# Fonte_Chaveada_ISL6236.net
KiCad netlist of a schematic drawn in Altium Designer
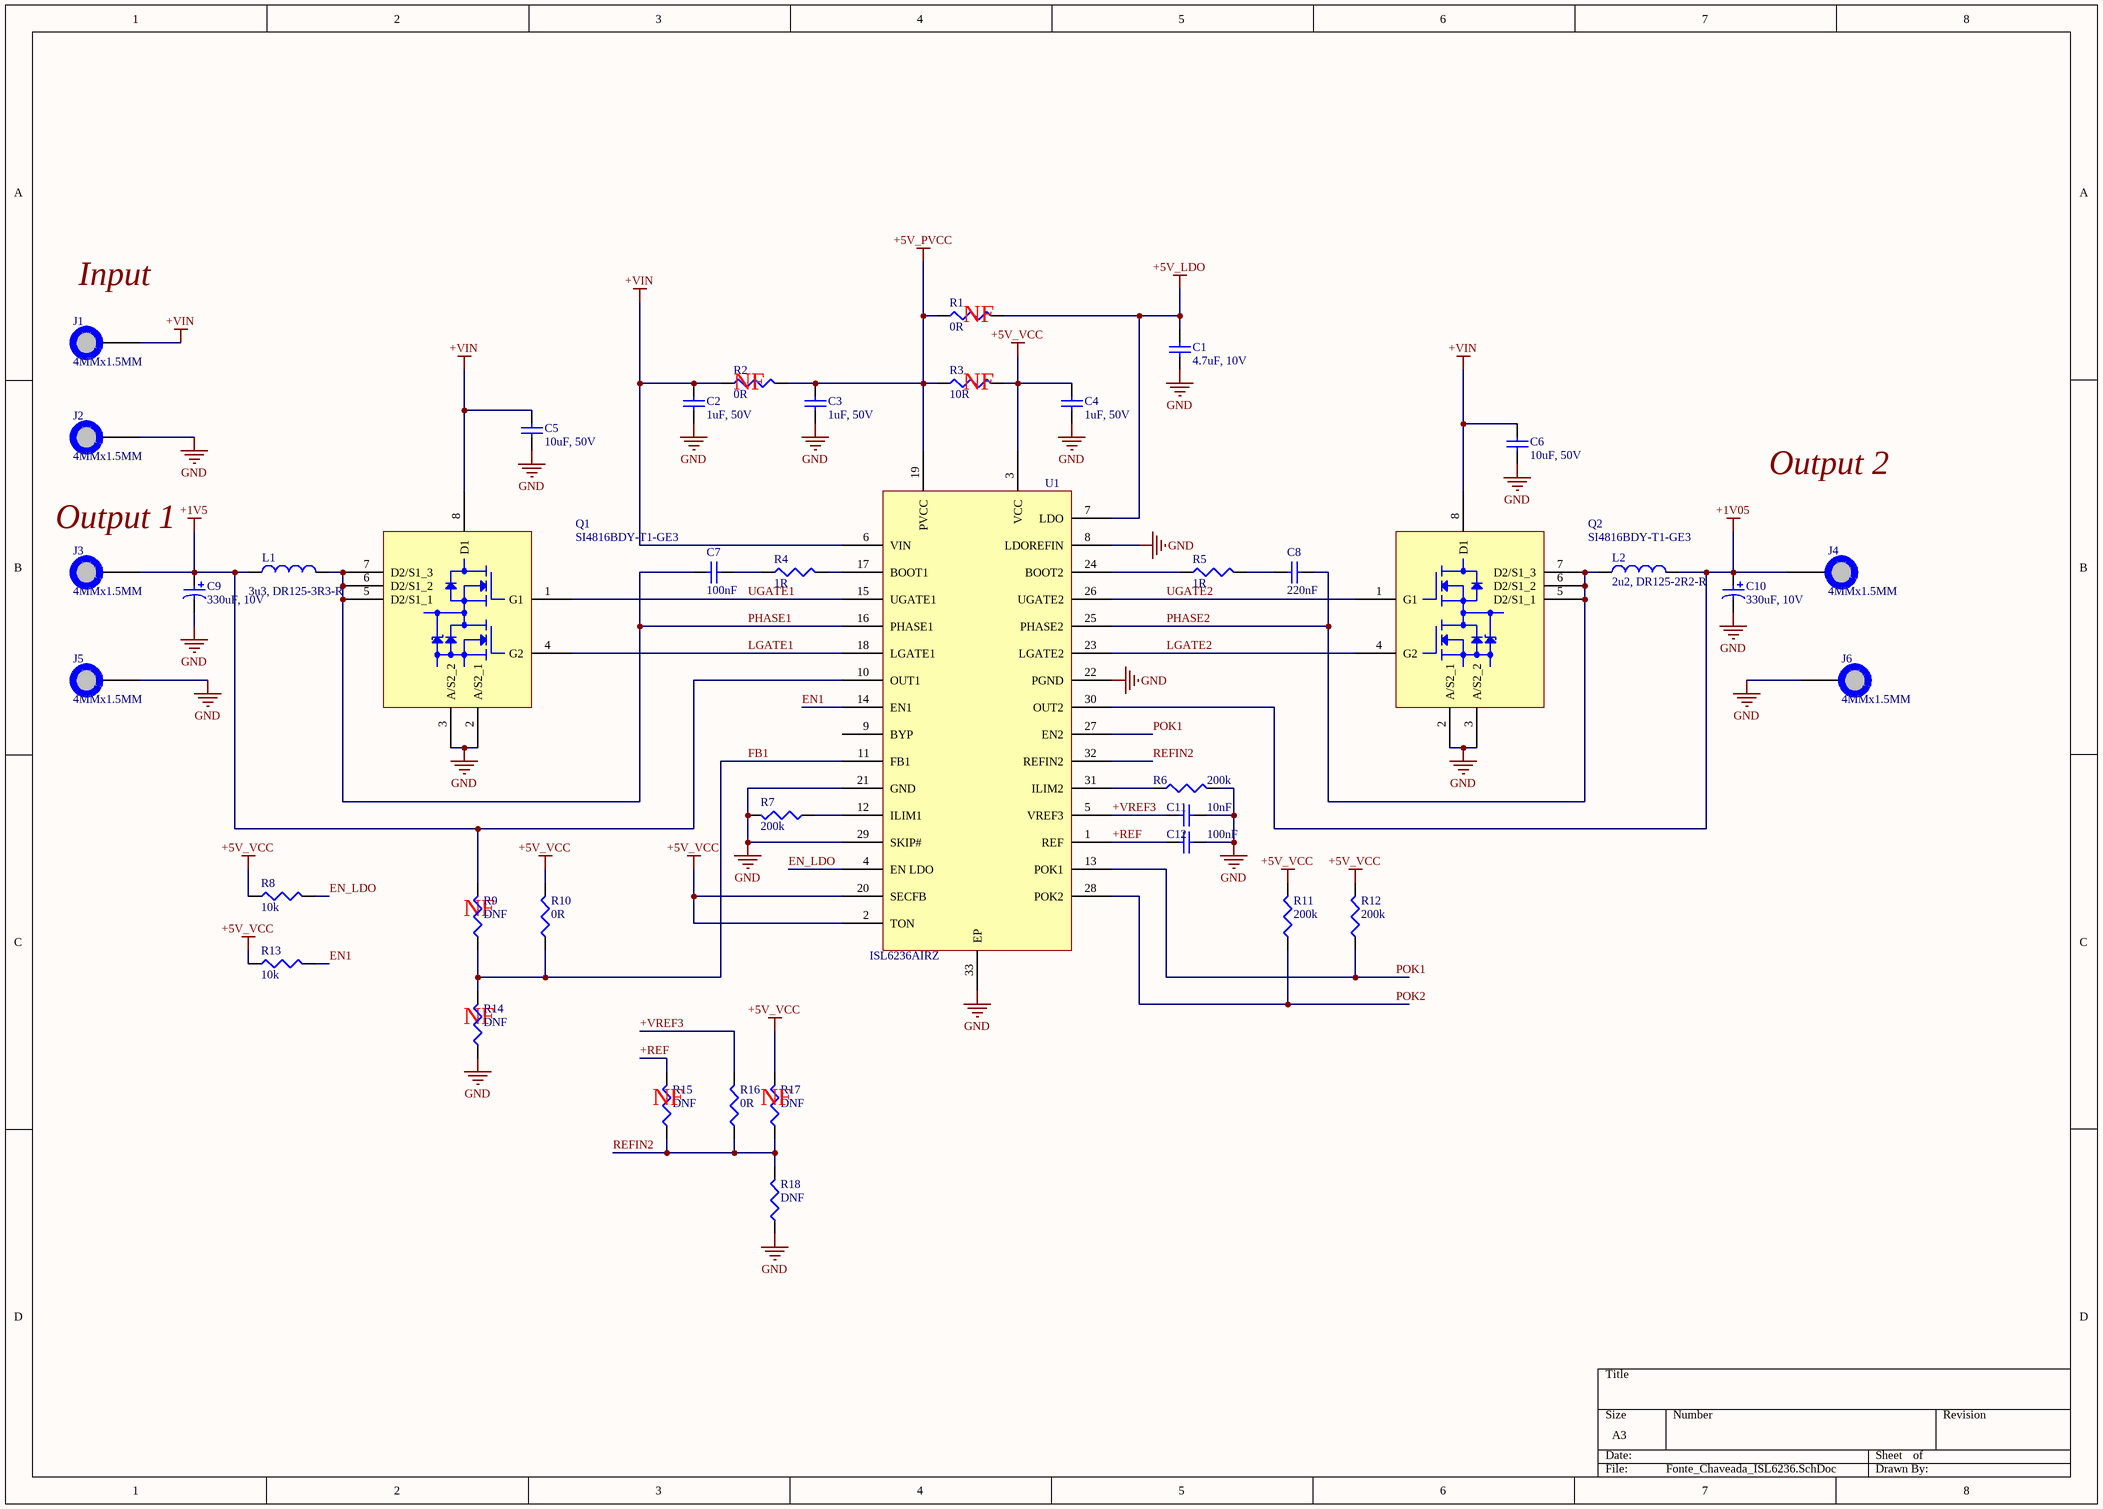
[diagram p0: Fonte_Chaveada_ISL6236.SchDoc]

(export (version "E")
  (design (tool "Eeschema 10.0.6"))
  (components
    (comp (ref "C1")
      (value "4.7uF, 10V")
      (footprint "C1206")
      (fields
        (field (name "MANUFACTURER") "TDK")
        (field (name "MANUFACTURER PART NUMBER") "C3216X5R1A475K")
        (field (name "TOLERANCE") "10%")
      )
      (libsource (lib "Fonte_Chaveada_ISL6236") (part "C3216X5R1A475K"))
    )
    (comp (ref "C2")
      (value "1uF, 50V")
      (footprint "C0805")
      (description "CAP CER 1UF 50V X7R 0805")
      (fields
        (field (name "MANUFACTURER") "TDK")
        (field (name "MANUFACTURER PART NUMBER") "C2012X7R1H105K125AB")
      )
      (libsource (lib "Fonte_Chaveada_ISL6236") (part "C2012X7R1H105K125AB"))
    )
    (comp (ref "C3")
      (value "1uF, 50V")
      (footprint "C0805")
      (description "CAP CER 1UF 50V X7R 0805")
      (fields
        (field (name "MANUFACTURER") "TDK")
        (field (name "MANUFACTURER PART NUMBER") "C2012X7R1H105K125AB")
      )
      (libsource (lib "Fonte_Chaveada_ISL6236") (part "C2012X7R1H105K125AB"))
    )
    (comp (ref "C4")
      (value "1uF, 50V")
      (footprint "C0805")
      (description "CAP CER 1UF 50V X7R 0805")
      (fields
        (field (name "MANUFACTURER") "TDK")
        (field (name "MANUFACTURER PART NUMBER") "C2012X7R1H105K125AB")
      )
      (libsource (lib "Fonte_Chaveada_ISL6236") (part "C2012X7R1H105K125AB"))
    )
    (comp (ref "C5")
      (value "10uF, 50V")
      (footprint "C1210")
      (description "CAP CER 10UF 50V X5R 1210")
      (fields
        (field (name "MANUFACTURER") "Taiyo Yuden")
        (field (name "MANUFACTURER PART NUMBER") "UMK325BJ106MM-T")
      )
      (libsource (lib "Fonte_Chaveada_ISL6236") (part "UMK325BJ106MM-T"))
    )
    (comp (ref "C6")
      (value "10uF, 50V")
      (footprint "C1210")
      (description "CAP CER 10UF 50V X5R 1210")
      (fields
        (field (name "MANUFACTURER") "Taiyo Yuden")
        (field (name "MANUFACTURER PART NUMBER") "UMK325BJ106MM-T")
      )
      (libsource (lib "Fonte_Chaveada_ISL6236") (part "UMK325BJ106MM-T"))
    )
    (comp (ref "C7")
      (value "100nF")
      (footprint "C0805")
      (description "CAP CER 0.1UF 50V X7R 0805")
      (fields
        (field (name "MANUFACTURER") "TDK")
        (field (name "MANUFACTURER PART NUMBER") "C2012X7R1H104K085AA")
      )
      (libsource (lib "Fonte_Chaveada_ISL6236") (part "C2012X7R1H104K085AA"))
    )
    (comp (ref "C8")
      (value "220nF")
      (footprint "C0805")
      (description "CAP CER 0.22UF 50V X7R 0805")
      (fields
        (field (name "MANUFACTURER") "TDK")
        (field (name "MANUFACTURER PART NUMBER") "C2012X7R1H224K125AA")
      )
      (libsource (lib "Fonte_Chaveada_ISL6236") (part "C2012X7R1H224K125AA"))
    )
    (comp (ref "C9")
      (value "330uF, 10V")
      (footprint "7343-43")
      (description "Tantalum Capacitors - Polymer SMD 330uF 10volts 20%")
      (fields
        (field (name "MANUFACTURER") "KEMET")
        (field (name "MANUFACTURER PART NUMBER") "T530X337M010ATE004")
      )
      (libsource (lib "Fonte_Chaveada_ISL6236") (part "T530X337M010ATE004"))
    )
    (comp (ref "C10")
      (value "330uF, 10V")
      (footprint "7343-43")
      (description "Tantalum Capacitors - Polymer SMD 330uF 10volts 20%")
      (fields
        (field (name "MANUFACTURER") "KEMET")
        (field (name "MANUFACTURER PART NUMBER") "T530X337M010ATE004")
      )
      (libsource (lib "Fonte_Chaveada_ISL6236") (part "T530X337M010ATE004"))
    )
    (comp (ref "C11")
      (value "10nF")
      (footprint "C0805")
      (description "CAP CER 10000PF 50V X7R 0805")
      (fields
        (field (name "MANUFACTURER") "Vishay Vitramon")
        (field (name "MANUFACTURER PART NUMBER") "VJ0805Y103KNAAO")
      )
      (libsource (lib "Fonte_Chaveada_ISL6236") (part "VJ0805Y103KNAAO"))
    )
    (comp (ref "C12")
      (value "100nF")
      (footprint "C0805")
      (description "CAP CER 0.1UF 50V X7R 0805")
      (fields
        (field (name "MANUFACTURER") "TDK")
        (field (name "MANUFACTURER PART NUMBER") "C2012X7R1H104K085AA")
      )
      (libsource (lib "Fonte_Chaveada_ISL6236") (part "C2012X7R1H104K085AA"))
    )
    (comp (ref "J1")
      (value "4MMx1.5MM")
      (footprint "PAD")
      (libsource (lib "Fonte_Chaveada_ISL6236") (part "PAD com furo"))
    )
    (comp (ref "J2")
      (value "4MMx1.5MM")
      (footprint "PAD")
      (libsource (lib "Fonte_Chaveada_ISL6236") (part "PAD com furo"))
    )
    (comp (ref "J3")
      (value "4MMx1.5MM")
      (footprint "PAD")
      (libsource (lib "Fonte_Chaveada_ISL6236") (part "PAD com furo"))
    )
    (comp (ref "J4")
      (value "4MMx1.5MM")
      (footprint "PAD")
      (libsource (lib "Fonte_Chaveada_ISL6236") (part "PAD com furo"))
    )
    (comp (ref "J5")
      (value "4MMx1.5MM")
      (footprint "PAD")
      (libsource (lib "Fonte_Chaveada_ISL6236") (part "PAD com furo"))
    )
    (comp (ref "J6")
      (value "4MMx1.5MM")
      (footprint "PAD")
      (libsource (lib "Fonte_Chaveada_ISL6236") (part "PAD com furo"))
    )
    (comp (ref "L1")
      (value "3u3, DR125-3R3-R")
      (footprint "DR125")
      (description "COILTRONICS   DR125-3R3-R   Surface Mount Power Inductor, DR Series, 3.3 H,  20%, Shielded, 9.26 A")
      (fields
        (field (name "MANUFACTURER") "Eaton Coiltronics")
        (field (name "MANUFACTURER PART NUMBER") "DR125-3R3-R")
      )
      (libsource (lib "Fonte_Chaveada_ISL6236") (part "DR125-3R3-R"))
    )
    (comp (ref "L2")
      (value "2u2, DR125-2R2-R")
      (footprint "DR125")
      (description "Fixed Inductors 2.2uH 15A 0.0045ohms")
      (fields
        (field (name "MANUFACTURER") "Eaton Cooper")
        (field (name "MANUFACTURER PART NUMBER") "DR125-2R2-R")
      )
      (libsource (lib "Fonte_Chaveada_ISL6236") (part "DR125-2R2-R"))
    )
    (comp (ref "Q1")
      (value "SI4816BDY-T1-GE3")
      (footprint "SO-8")
      (description "MOSFET 2N-CH 30V 5.8A 8-SOIC")
      (fields (field (name "MANUFACTURER") "Vishay Siliconix"))
      (libsource (lib "Fonte_Chaveada_ISL6236") (part "SI4816BDY-T1-GE3"))
    )
    (comp (ref "Q2")
      (value "SI4816BDY-T1-GE3")
      (footprint "SO-8")
      (description "MOSFET 2N-CH 30V 5.8A 8-SOIC")
      (fields (field (name "MANUFACTURER") "Vishay Siliconix"))
      (libsource (lib "") (part "SI4816BDY-T1-GE3_1"))
    )
    (comp (ref "R1")
      (value "0R")
      (footprint "R0805")
      (description "Res Thick Film 0805 0 Ohm Molded SMD SMD Embossed Carrier T/R")
      (fields
        (field (name "MANUFACTURER") "Panasonic")
        (field (name "MANUFACTURER PART NUMBER") "ERJ6GEY0R00V")
      )
      (libsource (lib "Fonte_Chaveada_ISL6236") (part "ERJ6GEY0R00V"))
    )
    (comp (ref "R2")
      (value "0R")
      (footprint "R0805")
      (description "Res Thick Film 0805 0 Ohm Molded SMD SMD Embossed Carrier T/R")
      (fields
        (field (name "MANUFACTURER") "Panasonic")
        (field (name "MANUFACTURER PART NUMBER") "ERJ6GEY0R00V")
      )
      (libsource (lib "Fonte_Chaveada_ISL6236") (part "ERJ6GEY0R00V"))
    )
    (comp (ref "R3")
      (value "10R")
      (footprint "R0805")
      (description "Res Thick Film 0805 10 Ohm 5% 0.125W(1/8W) ±200ppm/C Molded SMD Automotive Punched T/R")
      (fields
        (field (name "MANUFACTURER") "Panasonic")
        (field (name "MANUFACTURER PART NUMBER") "ERJ6GEYJ100V")
      )
      (libsource (lib "Fonte_Chaveada_ISL6236") (part "ERJ6GEYJ100V"))
    )
    (comp (ref "R4")
      (value "1R")
      (footprint "R0805")
      (description "Res Thick Film 0805 1 Ohm 1% 0.125W(1/8W) ±200ppm/C Molded SMD Automotive Punched T/R")
      (fields
        (field (name "MANUFACTURER") "Panasonic")
        (field (name "MANUFACTURER PART NUMBER") "ERJ6RQF1R0V")
      )
      (libsource (lib "Fonte_Chaveada_ISL6236") (part "ERJ6RQF1R0V"))
    )
    (comp (ref "R5")
      (value "1R")
      (footprint "R0805")
      (description "Res Thick Film 0805 1 Ohm 1% 0.125W(1/8W) ±200ppm/C Molded SMD Automotive Punched T/R")
      (fields
        (field (name "MANUFACTURER") "Panasonic")
        (field (name "MANUFACTURER PART NUMBER") "ERJ6RQF1R0V")
      )
      (libsource (lib "Fonte_Chaveada_ISL6236") (part "ERJ6RQF1R0V"))
    )
    (comp (ref "R6")
      (value "200k")
      (footprint "R0805")
      (description "Res Thick Film 0805 200K Ohm 1% 1/8W ±100ppm/C Molded SMD Punched Carrier T/R")
      (fields
        (field (name "MANUFACTURER") "Panasonic")
        (field (name "MANUFACTURER PART NUMBER") "ERJ6ENF2003V")
      )
      (libsource (lib "Fonte_Chaveada_ISL6236") (part "ERJ6ENF2003V"))
    )
    (comp (ref "R7")
      (value "200k")
      (footprint "R0805")
      (description "Res Thick Film 0805 200K Ohm 1% 1/8W ±100ppm/C Molded SMD Punched Carrier T/R")
      (fields
        (field (name "MANUFACTURER") "Panasonic")
        (field (name "MANUFACTURER PART NUMBER") "ERJ6ENF2003V")
      )
      (libsource (lib "Fonte_Chaveada_ISL6236") (part "ERJ6ENF2003V"))
    )
    (comp (ref "R8")
      (value "10k")
      (footprint "R0805")
      (description "Res Thick Film 0805 10K Ohm 5% 0.125W(1/8W) ±200ppm/C Molded SMD Automotive Punched T/R")
      (fields
        (field (name "MANUFACTURER") "Panasonic")
        (field (name "MANUFACTURER PART NUMBER") "ERJ6GEYJ103V")
      )
      (libsource (lib "Fonte_Chaveada_ISL6236") (part "ERJ6GEYJ103V"))
    )
    (comp (ref "R9")
      (value "DNF")
      (footprint "R0805")
      (libsource (lib "Fonte_Chaveada_ISL6236") (part "RES"))
    )
    (comp (ref "R10")
      (value "0R")
      (footprint "R0805")
      (description "Res Thick Film 0805 0 Ohm Molded SMD SMD Embossed Carrier T/R")
      (fields
        (field (name "MANUFACTURER") "Panasonic")
        (field (name "MANUFACTURER PART NUMBER") "ERJ6GEY0R00V")
      )
      (libsource (lib "Fonte_Chaveada_ISL6236") (part "ERJ6GEY0R00V"))
    )
    (comp (ref "R11")
      (value "200k")
      (footprint "R0805")
      (description "Res Thick Film 0805 200K Ohm 1% 1/8W ±100ppm/C Molded SMD Punched Carrier T/R")
      (fields
        (field (name "MANUFACTURER") "Panasonic")
        (field (name "MANUFACTURER PART NUMBER") "ERJ6ENF2003V")
      )
      (libsource (lib "Fonte_Chaveada_ISL6236") (part "ERJ6ENF2003V"))
    )
    (comp (ref "R12")
      (value "200k")
      (footprint "R0805")
      (description "Res Thick Film 0805 200K Ohm 1% 1/8W ±100ppm/C Molded SMD Punched Carrier T/R")
      (fields
        (field (name "MANUFACTURER") "Panasonic")
        (field (name "MANUFACTURER PART NUMBER") "ERJ6ENF2003V")
      )
      (libsource (lib "Fonte_Chaveada_ISL6236") (part "ERJ6ENF2003V"))
    )
    (comp (ref "R13")
      (value "10k")
      (footprint "R0805")
      (description "Res Thick Film 0805 10K Ohm 5% 0.125W(1/8W) ±200ppm/C Molded SMD Automotive Punched T/R")
      (fields
        (field (name "MANUFACTURER") "Panasonic")
        (field (name "MANUFACTURER PART NUMBER") "ERJ6GEYJ103V")
      )
      (libsource (lib "Fonte_Chaveada_ISL6236") (part "ERJ6GEYJ103V"))
    )
    (comp (ref "R14")
      (value "DNF")
      (footprint "R0805")
      (libsource (lib "Fonte_Chaveada_ISL6236") (part "RES"))
    )
    (comp (ref "R15")
      (value "DNF")
      (footprint "R0805")
      (libsource (lib "Fonte_Chaveada_ISL6236") (part "RES"))
    )
    (comp (ref "R16")
      (value "0R")
      (footprint "R0805")
      (description "Res Thick Film 0805 0 Ohm Molded SMD SMD Embossed Carrier T/R")
      (fields
        (field (name "MANUFACTURER") "Panasonic")
        (field (name "MANUFACTURER PART NUMBER") "ERJ6GEY0R00V")
      )
      (libsource (lib "Fonte_Chaveada_ISL6236") (part "ERJ6GEY0R00V"))
    )
    (comp (ref "R17")
      (value "DNF")
      (footprint "R0805")
      (libsource (lib "Fonte_Chaveada_ISL6236") (part "RES"))
    )
    (comp (ref "R18")
      (value "DNF")
      (footprint "R0805")
      (libsource (lib "Fonte_Chaveada_ISL6236") (part "RES"))
    )
    (comp (ref "U1")
      (value "ISL6236AIRZ")
      (footprint "L32.5x5B")
      (description "IC MAIN PWR CTRLR QUAD 32-QFN")
      (fields (field (name "MANUFACTURER") "Intersil"))
      (libsource (lib "Fonte_Chaveada_ISL6236") (part "ISL6236AIRZ"))
    )
  )
  (nets
    (net (code "1") (name "+1V05") (class "Default")
      (node (ref "C10") (pin "1") (pinfunction "1_1") (pintype "passive"))
      (node (ref "J4") (pin "1") (pinfunction "1_1") (pintype "passive"))
      (node (ref "L2") (pin "2") (pinfunction "2_2") (pintype "passive"))
      (node (ref "U1") (pin "30") (pinfunction "OUT2_30") (pintype "passive"))
    )
    (net (code "2") (name "+1V5") (class "Default")
      (node (ref "C9") (pin "1") (pinfunction "1_1") (pintype "passive"))
      (node (ref "J3") (pin "1") (pinfunction "1_1") (pintype "passive"))
      (node (ref "L1") (pin "1") (pinfunction "1_1") (pintype "passive"))
      (node (ref "R9") (pin "2") (pinfunction "2_2") (pintype "passive"))
      (node (ref "U1") (pin "10") (pinfunction "OUT1_10") (pintype "passive"))
    )
    (net (code "3") (name "+5V_LDO") (class "Default")
      (node (ref "C1") (pin "2") (pinfunction "2_2") (pintype "passive"))
      (node (ref "R1") (pin "2") (pinfunction "2_2") (pintype "passive"))
      (node (ref "U1") (pin "7") (pinfunction "LDO_7") (pintype "passive"))
    )
    (net (code "4") (name "+5V_PVCC") (class "Default")
      (node (ref "C3") (pin "2") (pinfunction "2_2") (pintype "passive"))
      (node (ref "R1") (pin "1") (pinfunction "1_1") (pintype "passive"))
      (node (ref "R2") (pin "2") (pinfunction "2_2") (pintype "passive"))
      (node (ref "R3") (pin "1") (pinfunction "1_1") (pintype "passive"))
      (node (ref "U1") (pin "19") (pinfunction "PVCC_19") (pintype "passive"))
    )
    (net (code "5") (name "+5V_VCC") (class "Default")
      (node (ref "C4") (pin "2") (pinfunction "2_2") (pintype "passive"))
      (node (ref "R10") (pin "2") (pinfunction "2_2") (pintype "passive"))
      (node (ref "R11") (pin "2") (pinfunction "2_2") (pintype "passive"))
      (node (ref "R12") (pin "2") (pinfunction "2_2") (pintype "passive"))
      (node (ref "R13") (pin "1") (pinfunction "1_1") (pintype "passive"))
      (node (ref "R17") (pin "2") (pinfunction "2_2") (pintype "passive"))
      (node (ref "R3") (pin "2") (pinfunction "2_2") (pintype "passive"))
      (node (ref "R8") (pin "1") (pinfunction "1_1") (pintype "passive"))
      (node (ref "U1") (pin "2") (pinfunction "TON_2") (pintype "passive"))
      (node (ref "U1") (pin "20") (pinfunction "SECFB_20") (pintype "passive"))
      (node (ref "U1") (pin "3") (pinfunction "VCC_3") (pintype "passive"))
    )
    (net (code "6") (name "+VIN") (class "Default")
      (node (ref "C2") (pin "2") (pinfunction "2_2") (pintype "passive"))
      (node (ref "C5") (pin "2") (pinfunction "2_2") (pintype "passive"))
      (node (ref "C6") (pin "2") (pinfunction "2_2") (pintype "passive"))
      (node (ref "J1") (pin "1") (pinfunction "1_1") (pintype "passive"))
      (node (ref "Q1") (pin "8") (pinfunction "D1_8") (pintype "passive"))
      (node (ref "Q2") (pin "8") (pinfunction "D1_8") (pintype "passive"))
      (node (ref "R2") (pin "1") (pinfunction "1_1") (pintype "passive"))
      (node (ref "U1") (pin "6") (pinfunction "VIN_6") (pintype "passive"))
    )
    (net (code "7") (name "/+REF") (class "Default")
      (node (ref "C12") (pin "1") (pinfunction "1_1") (pintype "passive"))
      (node (ref "R15") (pin "2") (pinfunction "2_2") (pintype "passive"))
      (node (ref "U1") (pin "1") (pinfunction "REF_1") (pintype "passive"))
    )
    (net (code "8") (name "/+VREF3") (class "Default")
      (node (ref "C11") (pin "1") (pinfunction "1_1") (pintype "passive"))
      (node (ref "R16") (pin "2") (pinfunction "2_2") (pintype "passive"))
      (node (ref "U1") (pin "5") (pinfunction "VREF3_5") (pintype "passive"))
    )
    (net (code "9") (name "/EN1") (class "Default")
      (node (ref "R13") (pin "2") (pinfunction "2_2") (pintype "passive"))
      (node (ref "U1") (pin "14") (pinfunction "EN1_14") (pintype "passive"))
    )
    (net (code "10") (name "/EN_LDO") (class "Default")
      (node (ref "R8") (pin "2") (pinfunction "2_2") (pintype "passive"))
      (node (ref "U1") (pin "4") (pinfunction "EN_LDO_4") (pintype "passive"))
    )
    (net (code "11") (name "/FB1") (class "Default")
      (node (ref "R10") (pin "1") (pinfunction "1_1") (pintype "passive"))
      (node (ref "R14") (pin "2") (pinfunction "2_2") (pintype "passive"))
      (node (ref "R9") (pin "1") (pinfunction "1_1") (pintype "passive"))
      (node (ref "U1") (pin "11") (pinfunction "FB1_11") (pintype "passive"))
    )
    (net (code "12") (name "/LGATE1") (class "Default")
      (node (ref "Q1") (pin "4") (pinfunction "G2_4") (pintype "passive"))
      (node (ref "U1") (pin "18") (pinfunction "LGATE1_18") (pintype "passive"))
    )
    (net (code "13") (name "/LGATE2") (class "Default")
      (node (ref "Q2") (pin "4") (pinfunction "G2_4") (pintype "passive"))
      (node (ref "U1") (pin "23") (pinfunction "LGATE2_23") (pintype "passive"))
    )
    (net (code "14") (name "/PHASE1") (class "Default")
      (node (ref "C7") (pin "1") (pinfunction "1_1") (pintype "passive"))
      (node (ref "L1") (pin "2") (pinfunction "2_2") (pintype "passive"))
      (node (ref "Q1") (pin "5") (pinfunction "D2/S1_1_5") (pintype "passive"))
      (node (ref "Q1") (pin "6") (pinfunction "D2/S1_2_6") (pintype "passive"))
      (node (ref "Q1") (pin "7") (pinfunction "D2/S1_3_7") (pintype "passive"))
      (node (ref "U1") (pin "16") (pinfunction "PHASE1_16") (pintype "passive"))
    )
    (net (code "15") (name "/PHASE2") (class "Default")
      (node (ref "C8") (pin "2") (pinfunction "2_2") (pintype "passive"))
      (node (ref "L2") (pin "1") (pinfunction "1_1") (pintype "passive"))
      (node (ref "Q2") (pin "5") (pinfunction "D2/S1_1_5") (pintype "passive"))
      (node (ref "Q2") (pin "6") (pinfunction "D2/S1_2_6") (pintype "passive"))
      (node (ref "Q2") (pin "7") (pinfunction "D2/S1_3_7") (pintype "passive"))
      (node (ref "U1") (pin "25") (pinfunction "PHASE2_25") (pintype "passive"))
    )
    (net (code "16") (name "/POK1") (class "Default")
      (node (ref "R12") (pin "1") (pinfunction "1_1") (pintype "passive"))
      (node (ref "U1") (pin "13") (pinfunction "POK1_13") (pintype "passive"))
      (node (ref "U1") (pin "27") (pinfunction "EN2_27") (pintype "passive"))
    )
    (net (code "17") (name "/POK2") (class "Default")
      (node (ref "R11") (pin "1") (pinfunction "1_1") (pintype "passive"))
      (node (ref "U1") (pin "28") (pinfunction "POK2_28") (pintype "passive"))
    )
    (net (code "18") (name "/REFIN2") (class "Default")
      (node (ref "R15") (pin "1") (pinfunction "1_1") (pintype "passive"))
      (node (ref "R16") (pin "1") (pinfunction "1_1") (pintype "passive"))
      (node (ref "R17") (pin "1") (pinfunction "1_1") (pintype "passive"))
      (node (ref "R18") (pin "2") (pinfunction "2_2") (pintype "passive"))
      (node (ref "U1") (pin "32") (pinfunction "REFIN2_32") (pintype "passive"))
    )
    (net (code "19") (name "/UGATE1") (class "Default")
      (node (ref "Q1") (pin "1") (pinfunction "G1_1") (pintype "passive"))
      (node (ref "U1") (pin "15") (pinfunction "UGATE1_15") (pintype "passive"))
    )
    (net (code "20") (name "/UGATE2") (class "Default")
      (node (ref "Q2") (pin "1") (pinfunction "G1_1") (pintype "passive"))
      (node (ref "U1") (pin "26") (pinfunction "UGATE2_26") (pintype "passive"))
    )
    (net (code "21") (name "GND") (class "Default")
      (node (ref "C1") (pin "1") (pinfunction "1_1") (pintype "passive"))
      (node (ref "C10") (pin "2") (pinfunction "2_2") (pintype "passive"))
      (node (ref "C11") (pin "2") (pinfunction "2_2") (pintype "passive"))
      (node (ref "C12") (pin "2") (pinfunction "2_2") (pintype "passive"))
      (node (ref "C2") (pin "1") (pinfunction "1_1") (pintype "passive"))
      (node (ref "C3") (pin "1") (pinfunction "1_1") (pintype "passive"))
      (node (ref "C4") (pin "1") (pinfunction "1_1") (pintype "passive"))
      (node (ref "C5") (pin "1") (pinfunction "1_1") (pintype "passive"))
      (node (ref "C6") (pin "1") (pinfunction "1_1") (pintype "passive"))
      (node (ref "C9") (pin "2") (pinfunction "2_2") (pintype "passive"))
      (node (ref "J2") (pin "1") (pinfunction "1_1") (pintype "passive"))
      (node (ref "J5") (pin "1") (pinfunction "1_1") (pintype "passive"))
      (node (ref "J6") (pin "1") (pinfunction "1_1") (pintype "passive"))
      (node (ref "Q1") (pin "2") (pinfunction "A/S2_1_2") (pintype "passive"))
      (node (ref "Q1") (pin "3") (pinfunction "A/S2_2_3") (pintype "passive"))
      (node (ref "Q2") (pin "2") (pinfunction "A/S2_1_2") (pintype "passive"))
      (node (ref "Q2") (pin "3") (pinfunction "A/S2_2_3") (pintype "passive"))
      (node (ref "R14") (pin "1") (pinfunction "1_1") (pintype "passive"))
      (node (ref "R18") (pin "1") (pinfunction "1_1") (pintype "passive"))
      (node (ref "R6") (pin "2") (pinfunction "2_2") (pintype "passive"))
      (node (ref "R7") (pin "2") (pinfunction "2_2") (pintype "passive"))
      (node (ref "U1") (pin "21") (pinfunction "GND_21") (pintype "passive"))
      (node (ref "U1") (pin "22") (pinfunction "PGND_22") (pintype "passive"))
      (node (ref "U1") (pin "29") (pinfunction "SKIP#_29") (pintype "passive"))
      (node (ref "U1") (pin "33") (pinfunction "EP_33") (pintype "passive"))
      (node (ref "U1") (pin "8") (pinfunction "LDOREFIN_8") (pintype "passive"))
    )
    (net (code "22") (name "Net-(C7-Pad2)") (class "Default")
      (node (ref "C7") (pin "2") (pinfunction "2_2") (pintype "passive"))
      (node (ref "R4") (pin "1") (pinfunction "1_1") (pintype "passive"))
    )
    (net (code "23") (name "Net-(C8-Pad1)") (class "Default")
      (node (ref "C8") (pin "1") (pinfunction "1_1") (pintype "passive"))
      (node (ref "R5") (pin "2") (pinfunction "2_2") (pintype "passive"))
    )
    (net (code "24") (name "Net-(U1-BOOT1)") (class "Default")
      (node (ref "R4") (pin "2") (pinfunction "2_2") (pintype "passive"))
      (node (ref "U1") (pin "17") (pinfunction "BOOT1_17") (pintype "passive"))
    )
    (net (code "25") (name "Net-(U1-BOOT2)") (class "Default")
      (node (ref "R5") (pin "1") (pinfunction "1_1") (pintype "passive"))
      (node (ref "U1") (pin "24") (pinfunction "BOOT2_24") (pintype "passive"))
    )
    (net (code "26") (name "Net-(U1-ILIM1)") (class "Default")
      (node (ref "R7") (pin "1") (pinfunction "1_1") (pintype "passive"))
      (node (ref "U1") (pin "12") (pinfunction "ILIM1_12") (pintype "passive"))
    )
    (net (code "27") (name "Net-(U1-ILIM2)") (class "Default")
      (node (ref "R6") (pin "1") (pinfunction "1_1") (pintype "passive"))
      (node (ref "U1") (pin "31") (pinfunction "ILIM2_31") (pintype "passive"))
    )
    (net (code "28") (name "unconnected-(U1-BYP-Pad9)") (class "Default")
      (node (ref "U1") (pin "9") (pinfunction "BYP_9") (pintype "passive"))
    )
  )
)
